# SolidStateDosimeter.net
KiCad netlist of a schematic drawn in Altium Designer
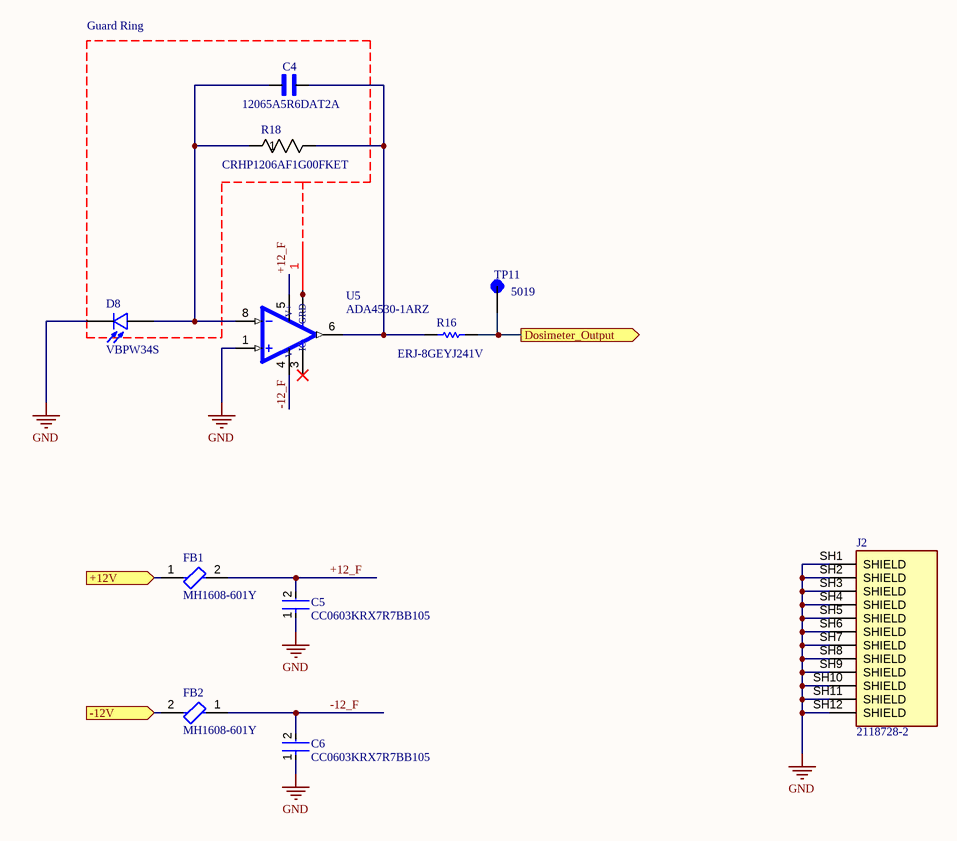
[diagram p0: SolidStateDosimeter.SchDoc]

(export (version "E")
  (design (tool "Eeschema 10.0.6"))
  (components
    (comp (ref "C4")
      (value "12065A5R6DAT2A")
      (footprint "12065A5R6DAT2A:CAPC3216X94N")
      (description "CAP CER 5.6PF 50V C0G/NP0 1206")
      (fields (field (name "MF") "{'manufacturer': u'AVX'}"))
      (libsource (lib "*") (part "12065A5R6DAT2A"))
    )
    (comp (ref "C5")
      (value "CC0603KRX7R7BB105")
      (footprint "FP-CC0603-DA-MFG")
      (description "CAP CER 1UF 16V X7R 0603")
      (fields (field (name "TOLERANCE") "0.1") (field (name "MANUFACTURER") "YAGEO"))
      (libsource (lib "Altium Content Vault") (part "11868f565c42a9108669ba33697ecf6"))
    )
    (comp (ref "C6")
      (value "CC0603KRX7R7BB105")
      (footprint "FP-CC0603-DA-MFG")
      (description "CAP CER 1UF 16V X7R 0603")
      (fields (field (name "TOLERANCE") "0.1") (field (name "MANUFACTURER") "YAGEO"))
      (libsource (lib "Altium Content Vault") (part "11868f565c42a9108669ba33697ecf6"))
    )
    (comp (ref "D8")
      (value "VBPW34S")
      (footprint "VBPW34S:XDCR_VBPW34S")
      (description "VBPW34SR Series 60 V 940 nm 50 mA 215 mW Surface Mount Silicon PIN Photodiode")
      (fields (field (name "MF") "{'manufacturer': u'Vishay'}"))
      (libsource (lib "*") (part "VBPW34S"))
    )
    (comp (ref "FB1")
      (value "MH1608-601Y")
      (footprint "FP-MH1608-MFG")
      (description "FERRITE BEAD 600 OHM 0603 1LN")
      (fields (field (name "TOLERANCE") "25%"))
      (libsource (lib "Altium Content Vault") (part "5f30dd21d616792df468990f7003faa"))
    )
    (comp (ref "FB2")
      (value "MH1608-601Y")
      (footprint "FP-MH1608-MFG")
      (description "FERRITE BEAD 600 OHM 0603 1LN")
      (fields (field (name "TOLERANCE") "25%"))
      (libsource (lib "Altium Content Vault") (part "5f30dd21d616792df468990f7003faa"))
    )
    (comp (ref "GR")
      (value "GUARD_RING")
      (footprint "Guard")
      (libsource (lib "guardRing") (part "Component_1"))
    )
    (comp (ref "J2")
      (value "2118728-2")
      (footprint "2118728-2:TE_2118728-2")
      (fields (field (name "MF") "{'manufacturer': u'TE Connectivity'}"))
      (libsource (lib "2118728-2") (part "2118728-2"))
    )
    (comp (ref "R16")
      (value "ERJ-8GEYJ241V")
      (footprint "RESC3216X70X50NL05T20")
      (fields (field (name "MANUFACTURER") "Panasonic"))
      (libsource (lib "Altium Content Vault") (part "RES"))
    )
    (comp (ref "R18")
      (value "CRHP1206AF1G00FKET")
      (footprint "RES_CRHP1206_VIS")
      (description "No Description Available")
      (libsource (lib "CRHP1206AF1G00FKET") (part "CRHP1206AF1G00FKET"))
    )
    (comp (ref "TP11")
      (value "5019")
      (footprint "5019:KEYSTONE_5019")
      (fields (field (name "MF") "{'manufacturer': u'Keystone Electronics'}"))
      (libsource (lib "*") (part "5019"))
    )
    (comp (ref "U5")
      (value "ADA4530-1ARZ")
      (footprint "SOIC127P600X175-8N")
      (fields (field (name "MF") "{'manufacturer': u'Analog Devices'}"))
      (libsource (lib "ADA4530-1ARZ") (part "ADA4530-1ARZ"))
    )
  )
  (nets
    (net (code "1") (name "/+12V") (class "Default")
      (node (ref "FB1") (pin "1") (pinfunction "1_1") (pintype "passive"))
    )
    (net (code "2") (name "/+12_F") (class "Default")
      (node (ref "C5") (pin "2") (pinfunction "2_2") (pintype "passive"))
      (node (ref "FB1") (pin "2") (pinfunction "2_2") (pintype "passive"))
      (node (ref "U5") (pin "5") (pinfunction "V+_5") (pintype "power_in"))
    )
    (net (code "3") (name "/-12V") (class "Default")
      (node (ref "FB2") (pin "2") (pinfunction "2_2") (pintype "passive"))
    )
    (net (code "4") (name "/-12_F") (class "Default")
      (node (ref "C6") (pin "2") (pinfunction "2_2") (pintype "passive"))
      (node (ref "FB2") (pin "1") (pinfunction "1_1") (pintype "passive"))
      (node (ref "U5") (pin "4") (pinfunction "V-_4") (pintype "power_in"))
    )
    (net (code "5") (name "/Dosimeter_Output") (class "Default")
      (node (ref "R16") (pin "2") (pinfunction "2_2") (pintype "passive"))
      (node (ref "TP11") (pin "TP") (pinfunction "TP_TP") (pintype "passive"))
    )
    (net (code "6") (name "GND") (class "Default")
      (node (ref "C5") (pin "1") (pinfunction "1_1") (pintype "passive"))
      (node (ref "C6") (pin "1") (pinfunction "1_1") (pintype "passive"))
      (node (ref "D8") (pin "K") (pinfunction "C_K") (pintype "passive"))
      (node (ref "J2") (pin "SH1") (pinfunction "SHIELD_SH1") (pintype "passive"))
      (node (ref "J2") (pin "SH10") (pinfunction "SHIELD_SH10") (pintype "passive"))
      (node (ref "J2") (pin "SH11") (pinfunction "SHIELD_SH11") (pintype "passive"))
      (node (ref "J2") (pin "SH12") (pinfunction "SHIELD_SH12") (pintype "passive"))
      (node (ref "J2") (pin "SH2") (pinfunction "SHIELD_SH2") (pintype "passive"))
      (node (ref "J2") (pin "SH3") (pinfunction "SHIELD_SH3") (pintype "passive"))
      (node (ref "J2") (pin "SH4") (pinfunction "SHIELD_SH4") (pintype "passive"))
      (node (ref "J2") (pin "SH5") (pinfunction "SHIELD_SH5") (pintype "passive"))
      (node (ref "J2") (pin "SH6") (pinfunction "SHIELD_SH6") (pintype "passive"))
      (node (ref "J2") (pin "SH7") (pinfunction "SHIELD_SH7") (pintype "passive"))
      (node (ref "J2") (pin "SH8") (pinfunction "SHIELD_SH8") (pintype "passive"))
      (node (ref "J2") (pin "SH9") (pinfunction "SHIELD_SH9") (pintype "passive"))
      (node (ref "U5") (pin "1") (pinfunction "+IN_1") (pintype "input"))
    )
    (net (code "7") (name "Net-(GR-15)") (class "Default")
      (node (ref "GR") (pin "1") (pinfunction "15_1") (pintype "passive"))
      (node (ref "U5") (pin "2") (pinfunction "GRD_2") (pintype "passive"))
      (node (ref "U5") (pin "7") (pinfunction "GRD_7") (pintype "passive"))
    )
    (net (code "8") (name "Net-(U5--IN)") (class "Default")
      (node (ref "C4") (pin "1") (pinfunction "1_1") (pintype "passive"))
      (node (ref "D8") (pin "A") (pinfunction "A_A") (pintype "passive"))
      (node (ref "R18") (pin "1") (pinfunction "1_1") (pintype "passive"))
      (node (ref "U5") (pin "8") (pinfunction "-IN_8") (pintype "input"))
    )
    (net (code "9") (name "Net-(U5-OUT)") (class "Default")
      (node (ref "C4") (pin "2") (pinfunction "2_2") (pintype "passive"))
      (node (ref "R16") (pin "1") (pinfunction "1_1") (pintype "passive"))
      (node (ref "R18") (pin "2") (pinfunction "2_2") (pintype "passive"))
      (node (ref "U5") (pin "6") (pinfunction "OUT_6") (pintype "output"))
    )
    (net (code "10") (name "unconnected-(U5-IC-Pad3)") (class "Default")
      (node (ref "U5") (pin "3") (pinfunction "IC_3") (pintype "passive+no_connect"))
    )
  )
)
